# Tricorder-BoosterPack.net
KiCad netlist of a schematic drawn in EAGLE
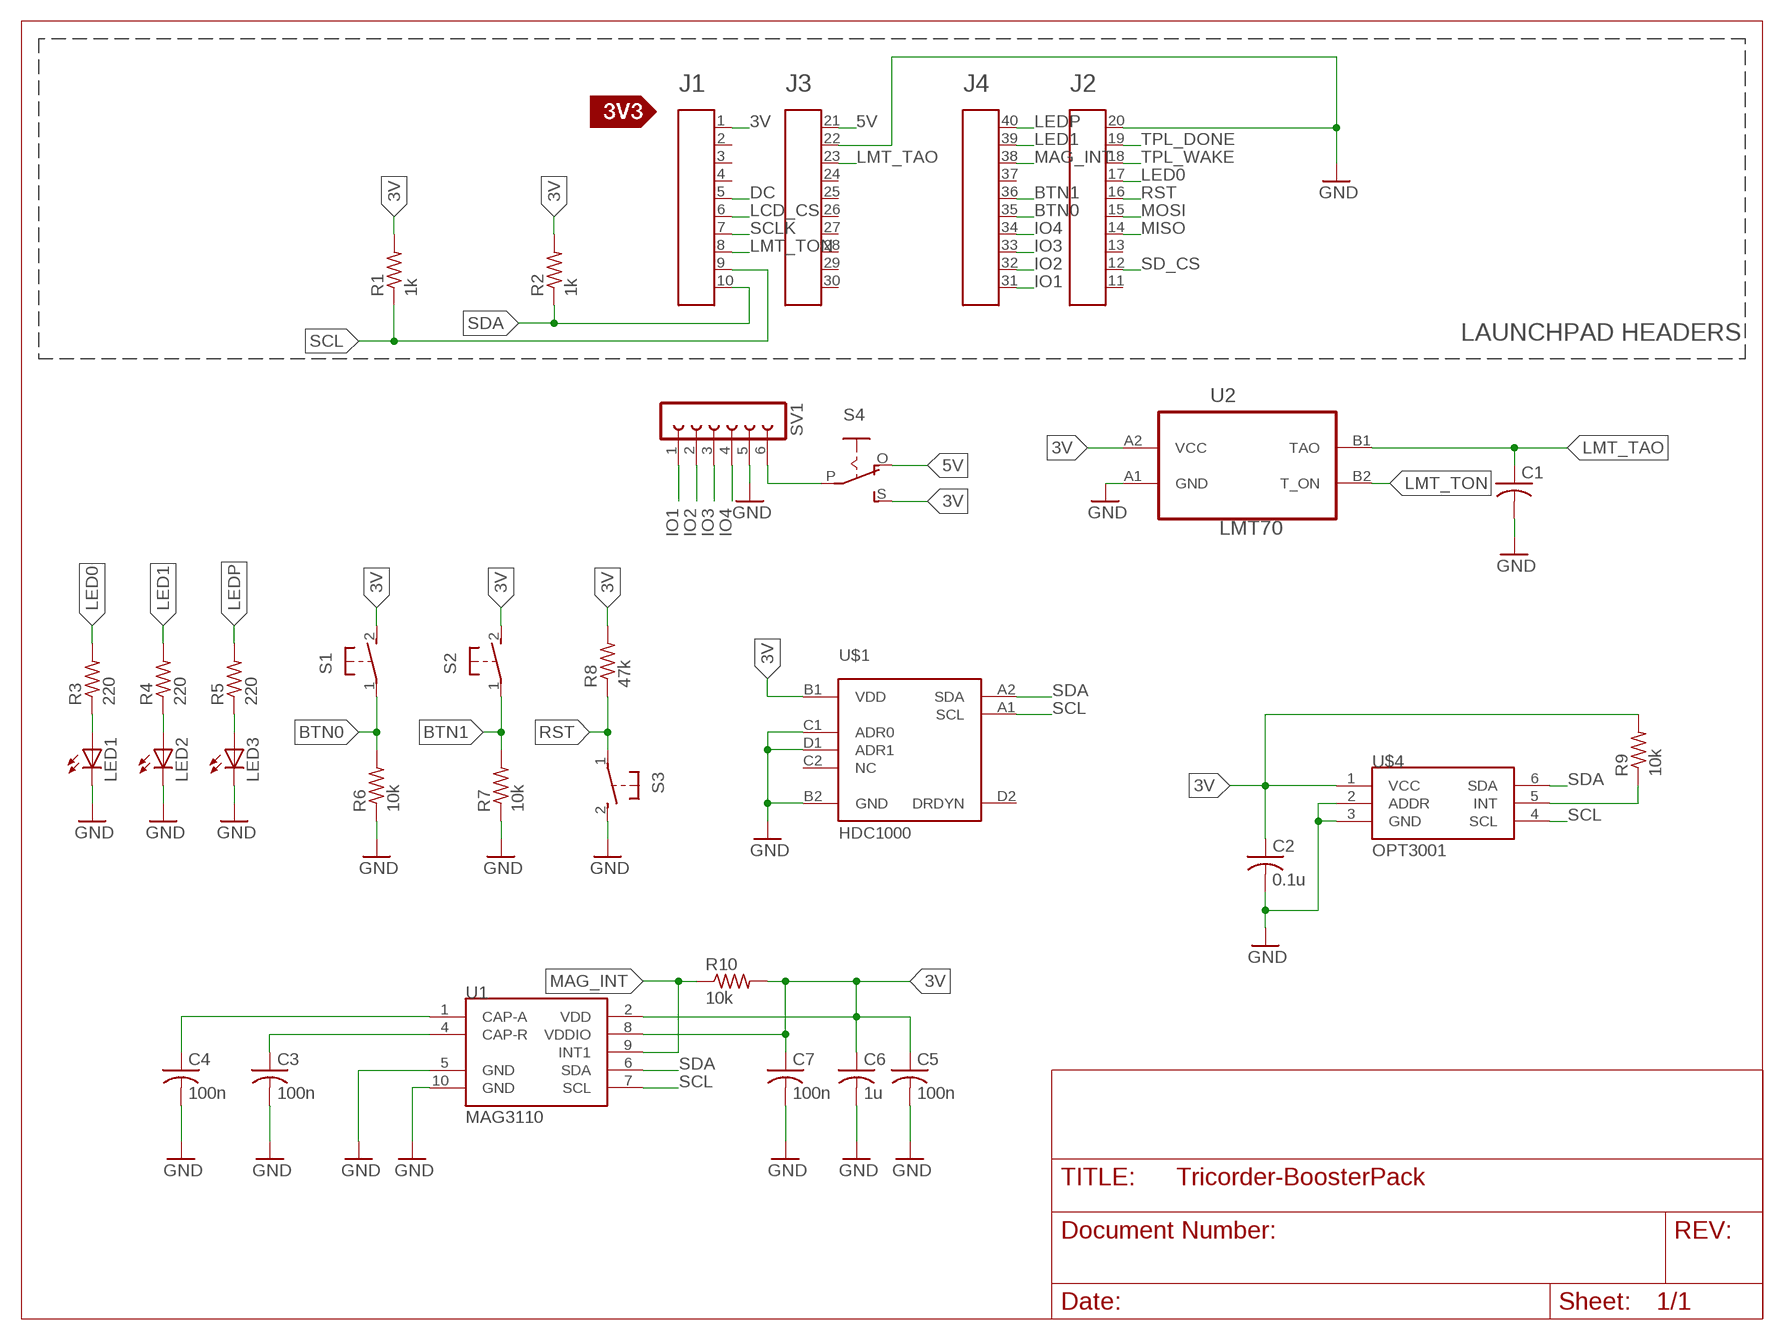
[diagram p0: schematic, sheet 1]

(export (version "E")
  (design (tool "Eeschema 10.0.6"))
  (components
    (comp (ref "A1")
      (value "HEADER4X10-BOOSTERPACK")
      (footprint "eagle-import:4X10-BOOSTERPACK")
      (libsource (lib "eagle-import") (part "HEADER4X10-BOOSTERPACK"))
    )
    (comp (ref "C1")
      (value "C-USC0603")
      (footprint "eagle-import:C0603")
      (libsource (lib "eagle-import") (part "C-USC0603"))
    )
    (comp (ref "C2")
      (value "0.1u")
      (footprint "eagle-import:C0603")
      (libsource (lib "eagle-import") (part "C-USC0603"))
    )
    (comp (ref "C3")
      (value "100n")
      (footprint "eagle-import:C0603")
      (libsource (lib "eagle-import") (part "C-USC0603"))
    )
    (comp (ref "C4")
      (value "100n")
      (footprint "eagle-import:C0603")
      (libsource (lib "eagle-import") (part "C-USC0603"))
    )
    (comp (ref "C5")
      (value "100n")
      (footprint "eagle-import:C0603")
      (libsource (lib "eagle-import") (part "C-USC0603"))
    )
    (comp (ref "C6")
      (value "1u")
      (footprint "eagle-import:C0603")
      (libsource (lib "eagle-import") (part "C-USC0603"))
    )
    (comp (ref "C7")
      (value "100n")
      (footprint "eagle-import:C0603")
      (libsource (lib "eagle-import") (part "C-USC0603"))
    )
    (comp (ref "LED1")
      (value "LEDCHIPLED_0603")
      (footprint "eagle-import:CHIPLED_0603")
      (libsource (lib "eagle-import") (part "LEDCHIPLED_0603"))
    )
    (comp (ref "LED2")
      (value "LEDCHIPLED_0603")
      (footprint "eagle-import:CHIPLED_0603")
      (libsource (lib "eagle-import") (part "LEDCHIPLED_0603"))
    )
    (comp (ref "LED3")
      (value "LEDCHIPLED_0603")
      (footprint "eagle-import:CHIPLED_0603")
      (libsource (lib "eagle-import") (part "LEDCHIPLED_0603"))
    )
    (comp (ref "R1")
      (value "1k")
      (footprint "eagle-import:R0603")
      (libsource (lib "eagle-import") (part "R-US_R0603"))
    )
    (comp (ref "R2")
      (value "1k")
      (footprint "eagle-import:R0603")
      (libsource (lib "eagle-import") (part "R-US_R0603"))
    )
    (comp (ref "R3")
      (value "220")
      (footprint "eagle-import:R0603")
      (libsource (lib "eagle-import") (part "R-US_R0603"))
    )
    (comp (ref "R4")
      (value "220")
      (footprint "eagle-import:R0603")
      (libsource (lib "eagle-import") (part "R-US_R0603"))
    )
    (comp (ref "R5")
      (value "220")
      (footprint "eagle-import:R0603")
      (libsource (lib "eagle-import") (part "R-US_R0603"))
    )
    (comp (ref "R6")
      (value "10k")
      (footprint "eagle-import:R0603")
      (libsource (lib "eagle-import") (part "R-US_R0603"))
    )
    (comp (ref "R7")
      (value "10k")
      (footprint "eagle-import:R0603")
      (libsource (lib "eagle-import") (part "R-US_R0603"))
    )
    (comp (ref "R8")
      (value "47k")
      (footprint "eagle-import:R0603")
      (libsource (lib "eagle-import") (part "R-US_R0603"))
    )
    (comp (ref "R9")
      (value "10k")
      (footprint "eagle-import:R0603")
      (libsource (lib "eagle-import") (part "R-US_R0603"))
    )
    (comp (ref "R10")
      (value "10k")
      (footprint "eagle-import:R0603")
      (libsource (lib "eagle-import") (part "R-US_R0603"))
    )
    (comp (ref "S1")
      (value "31-XX")
      (footprint "eagle-import:B3F-31XX")
      (libsource (lib "eagle-import") (part "31-XX"))
    )
    (comp (ref "S2")
      (value "31-XX")
      (footprint "eagle-import:B3F-31XX")
      (libsource (lib "eagle-import") (part "31-XX"))
    )
    (comp (ref "S3")
      (value "31-XX")
      (footprint "eagle-import:B3F-31XX")
      (libsource (lib "eagle-import") (part "31-XX"))
    )
    (comp (ref "S4")
      (value "EG1218S")
      (footprint "eagle-import:EG1218")
      (libsource (lib "eagle-import") (part "EG1218S"))
    )
    (comp (ref "SV1")
      (value "FE06-1")
      (footprint "eagle-import:FE06")
      (libsource (lib "eagle-import") (part "FE06-1"))
    )
    (comp (ref "U$1")
      (value "HDC1000")
      (footprint "eagle-import:DSBGA_8_YPA")
      (libsource (lib "eagle-import") (part "HDC1000"))
    )
    (comp (ref "U$3")
      (value "SILK_3V3_TAG")
      (footprint "eagle-import:SILK_3V3_TAG")
      (libsource (lib "eagle-import") (part "SILK_3V3_TAG"))
    )
    (comp (ref "U$4")
      (value "OPT3001")
      (footprint "eagle-import:SOT23-6")
      (libsource (lib "eagle-import") (part "OPT3001"))
    )
    (comp (ref "U1")
      (value "MAG3110")
      (footprint "eagle-import:DFN-10")
      (libsource (lib "eagle-import") (part "MAG3110"))
    )
    (comp (ref "U2")
      (value "LMT70LMT70")
      (footprint "eagle-import:BGA4C40P2X2_77X77X50")
      (fields (field (name "MPN") "LMT70"))
      (libsource (lib "eagle-import") (part "LMT70LMT70"))
    )
  )
  (nets
    (net (code "1") (name "/DC") (class "Default")
      (node (ref "A1") (pin "5") (pinfunction "P$5_5") (pintype "bidirectional"))
    )
    (net (code "2") (name "/IO1") (class "Default")
      (node (ref "A1") (pin "31") (pinfunction "P$31_31") (pintype "bidirectional"))
      (node (ref "SV1") (pin "1") (pinfunction "1_1") (pintype "passive"))
    )
    (net (code "3") (name "/IO2") (class "Default")
      (node (ref "A1") (pin "32") (pinfunction "P$32_32") (pintype "bidirectional"))
      (node (ref "SV1") (pin "2") (pinfunction "2_2") (pintype "passive"))
    )
    (net (code "4") (name "/IO3") (class "Default")
      (node (ref "A1") (pin "33") (pinfunction "P$33_33") (pintype "bidirectional"))
      (node (ref "SV1") (pin "3") (pinfunction "3_3") (pintype "passive"))
    )
    (net (code "5") (name "/IO4") (class "Default")
      (node (ref "A1") (pin "34") (pinfunction "P$34_34") (pintype "bidirectional"))
      (node (ref "SV1") (pin "4") (pinfunction "4_4") (pintype "passive"))
    )
    (net (code "6") (name "/LCD_CS") (class "Default")
      (node (ref "A1") (pin "6") (pinfunction "P$6_6") (pintype "bidirectional"))
    )
    (net (code "7") (name "/MISO") (class "Default")
      (node (ref "A1") (pin "14") (pinfunction "P$14_14") (pintype "bidirectional"))
    )
    (net (code "8") (name "/MOSI") (class "Default")
      (node (ref "A1") (pin "15") (pinfunction "P$15_15") (pintype "bidirectional"))
    )
    (net (code "9") (name "/SCLK") (class "Default")
      (node (ref "A1") (pin "7") (pinfunction "P$7_7") (pintype "bidirectional"))
    )
    (net (code "10") (name "/SD_CS") (class "Default")
      (node (ref "A1") (pin "12") (pinfunction "P$12_12") (pintype "bidirectional"))
    )
    (net (code "11") (name "/TPL_DONE") (class "Default")
      (node (ref "A1") (pin "19") (pinfunction "P$19_19") (pintype "bidirectional"))
    )
    (net (code "12") (name "/TPL_WAKE") (class "Default")
      (node (ref "A1") (pin "18") (pinfunction "P$18_18") (pintype "bidirectional"))
    )
    (net (code "13") (name "3V") (class "Default")
      (node (ref "A1") (pin "1") (pinfunction "P$1_1") (pintype "bidirectional"))
      (node (ref "C2") (pin "1") (pinfunction "1_1") (pintype "passive"))
      (node (ref "R1") (pin "2") (pinfunction "2_2") (pintype "passive"))
      (node (ref "R2") (pin "2") (pinfunction "2_2") (pintype "passive"))
      (node (ref "R8") (pin "2") (pinfunction "2_2") (pintype "passive"))
      (node (ref "R9") (pin "2") (pinfunction "2_2") (pintype "passive"))
      (node (ref "S1") (pin "2") (pinfunction "S_2") (pintype "passive"))
      (node (ref "S2") (pin "2") (pinfunction "S_2") (pintype "passive"))
      (node (ref "S4") (pin "S") (pinfunction "S_S") (pintype "passive"))
      (node (ref "U$1") (pin "B1") (pinfunction "VDD_B1") (pintype "power_in"))
      (node (ref "U$4") (pin "1") (pinfunction "VCC_1") (pintype "power_in"))
    )
    (net (code "14") (name "5V") (class "Default")
      (node (ref "A1") (pin "21") (pinfunction "P$21_21") (pintype "bidirectional"))
      (node (ref "S4") (pin "O") (pinfunction "O_O") (pintype "passive"))
    )
    (net (code "15") (name "BTN0") (class "Default")
      (node (ref "A1") (pin "35") (pinfunction "P$35_35") (pintype "bidirectional"))
      (node (ref "R6") (pin "2") (pinfunction "2_2") (pintype "passive"))
      (node (ref "S1") (pin "1") (pinfunction "P_1") (pintype "passive"))
    )
    (net (code "16") (name "BTN1") (class "Default")
      (node (ref "A1") (pin "36") (pinfunction "P$36_36") (pintype "bidirectional"))
      (node (ref "R7") (pin "2") (pinfunction "2_2") (pintype "passive"))
      (node (ref "S2") (pin "1") (pinfunction "P_1") (pintype "passive"))
    )
    (net (code "17") (name "GND") (class "Default")
      (node (ref "A1") (pin "20") (pinfunction "P$20_20") (pintype "bidirectional"))
      (node (ref "A1") (pin "22") (pinfunction "P$22_22") (pintype "bidirectional"))
      (node (ref "C1") (pin "2") (pinfunction "2_2") (pintype "passive"))
      (node (ref "C2") (pin "2") (pinfunction "2_2") (pintype "passive"))
      (node (ref "C3") (pin "2") (pinfunction "2_2") (pintype "passive"))
      (node (ref "C4") (pin "2") (pinfunction "2_2") (pintype "passive"))
      (node (ref "C5") (pin "2") (pinfunction "2_2") (pintype "passive"))
      (node (ref "C6") (pin "2") (pinfunction "2_2") (pintype "passive"))
      (node (ref "C7") (pin "2") (pinfunction "2_2") (pintype "passive"))
      (node (ref "LED1") (pin "C") (pinfunction "C_C") (pintype "passive"))
      (node (ref "LED2") (pin "C") (pinfunction "C_C") (pintype "passive"))
      (node (ref "LED3") (pin "C") (pinfunction "C_C") (pintype "passive"))
      (node (ref "R6") (pin "1") (pinfunction "1_1") (pintype "passive"))
      (node (ref "R7") (pin "1") (pinfunction "1_1") (pintype "passive"))
      (node (ref "S3") (pin "2") (pinfunction "S_2") (pintype "passive"))
      (node (ref "SV1") (pin "5") (pinfunction "5_5") (pintype "passive"))
      (node (ref "U$1") (pin "B2") (pinfunction "GND_B2") (pintype "power_in"))
      (node (ref "U$1") (pin "C1") (pinfunction "ADR0_C1") (pintype "input"))
      (node (ref "U$1") (pin "D1") (pinfunction "ADR1_D1") (pintype "input"))
      (node (ref "U$4") (pin "2") (pinfunction "ADDR_2") (pintype "input"))
      (node (ref "U$4") (pin "3") (pinfunction "GND_3") (pintype "power_in"))
      (node (ref "U1") (pin "10") (pinfunction "GND_10") (pintype "bidirectional"))
      (node (ref "U1") (pin "5") (pinfunction "GND_5") (pintype "bidirectional"))
      (node (ref "U2") (pin "A1") (pinfunction "GND_A1") (pintype "passive"))
    )
    (net (code "18") (name "LED0") (class "Default")
      (node (ref "A1") (pin "17") (pinfunction "P$17_17") (pintype "bidirectional"))
      (node (ref "R3") (pin "2") (pinfunction "2_2") (pintype "passive"))
    )
    (net (code "19") (name "LED1") (class "Default")
      (node (ref "A1") (pin "39") (pinfunction "P$39_39") (pintype "bidirectional"))
      (node (ref "R4") (pin "2") (pinfunction "2_2") (pintype "passive"))
    )
    (net (code "20") (name "LEDP") (class "Default")
      (node (ref "A1") (pin "40") (pinfunction "P$40_40") (pintype "bidirectional"))
      (node (ref "R5") (pin "2") (pinfunction "2_2") (pintype "passive"))
    )
    (net (code "21") (name "LMT_TAO") (class "Default")
      (node (ref "A1") (pin "23") (pinfunction "P$23_23") (pintype "bidirectional"))
      (node (ref "C1") (pin "1") (pinfunction "1_1") (pintype "passive"))
      (node (ref "U2") (pin "B1") (pinfunction "TAO_B1") (pintype "output"))
    )
    (net (code "22") (name "LMT_TON") (class "Default")
      (node (ref "A1") (pin "8") (pinfunction "P$8_8") (pintype "bidirectional"))
      (node (ref "U2") (pin "B2") (pinfunction "T_ON_B2") (pintype "input"))
    )
    (net (code "23") (name "MAG_INT") (class "Default")
      (node (ref "A1") (pin "38") (pinfunction "P$38_38") (pintype "bidirectional"))
      (node (ref "R10") (pin "1") (pinfunction "1_1") (pintype "passive"))
      (node (ref "U1") (pin "9") (pinfunction "INT1_9") (pintype "bidirectional"))
    )
    (net (code "24") (name "Net-(LED1-PadA)") (class "Default")
      (node (ref "LED1") (pin "A") (pinfunction "A_A") (pintype "passive"))
      (node (ref "R3") (pin "1") (pinfunction "1_1") (pintype "passive"))
    )
    (net (code "25") (name "Net-(LED2-PadA)") (class "Default")
      (node (ref "LED2") (pin "A") (pinfunction "A_A") (pintype "passive"))
      (node (ref "R4") (pin "1") (pinfunction "1_1") (pintype "passive"))
    )
    (net (code "26") (name "Net-(LED3-PadA)") (class "Default")
      (node (ref "LED3") (pin "A") (pinfunction "A_A") (pintype "passive"))
      (node (ref "R5") (pin "1") (pinfunction "1_1") (pintype "passive"))
    )
    (net (code "27") (name "Net-(S4-PadP)") (class "Default")
      (node (ref "S4") (pin "P") (pinfunction "P_P") (pintype "passive"))
      (node (ref "SV1") (pin "6") (pinfunction "6_6") (pintype "passive"))
    )
    (net (code "28") (name "Net-(U$4-INT)") (class "Default")
      (node (ref "R9") (pin "1") (pinfunction "1_1") (pintype "passive"))
      (node (ref "U$4") (pin "5") (pinfunction "INT_5") (pintype "output"))
    )
    (net (code "29") (name "Net-(U1-CAP-A)") (class "Default")
      (node (ref "C4") (pin "1") (pinfunction "1_1") (pintype "passive"))
      (node (ref "U1") (pin "1") (pinfunction "CAP-A_1") (pintype "bidirectional"))
    )
    (net (code "30") (name "Net-(U1-CAP-R)") (class "Default")
      (node (ref "C3") (pin "1") (pinfunction "1_1") (pintype "passive"))
      (node (ref "U1") (pin "4") (pinfunction "CAP-R_4") (pintype "bidirectional"))
    )
    (net (code "31") (name "Net-(U1-VDD)") (class "Default")
      (node (ref "C5") (pin "1") (pinfunction "1_1") (pintype "passive"))
      (node (ref "C6") (pin "1") (pinfunction "1_1") (pintype "passive"))
      (node (ref "C7") (pin "1") (pinfunction "1_1") (pintype "passive"))
      (node (ref "R10") (pin "2") (pinfunction "2_2") (pintype "passive"))
      (node (ref "U1") (pin "2") (pinfunction "VDD_2") (pintype "bidirectional"))
      (node (ref "U1") (pin "8") (pinfunction "VDDIO_8") (pintype "bidirectional"))
    )
    (net (code "32") (name "RST") (class "Default")
      (node (ref "A1") (pin "16") (pinfunction "P$16_16") (pintype "bidirectional"))
      (node (ref "R8") (pin "1") (pinfunction "1_1") (pintype "passive"))
      (node (ref "S3") (pin "1") (pinfunction "P_1") (pintype "passive"))
    )
    (net (code "33") (name "SCL") (class "Default")
      (node (ref "A1") (pin "9") (pinfunction "P$9_9") (pintype "bidirectional"))
      (node (ref "R1") (pin "1") (pinfunction "1_1") (pintype "passive"))
      (node (ref "U$1") (pin "A1") (pinfunction "SCL_A1") (pintype "input"))
      (node (ref "U$4") (pin "4") (pinfunction "SCL_4") (pintype "input"))
      (node (ref "U1") (pin "7") (pinfunction "SCL_7") (pintype "bidirectional"))
    )
    (net (code "34") (name "SDA") (class "Default")
      (node (ref "A1") (pin "10") (pinfunction "P$10_10") (pintype "bidirectional"))
      (node (ref "R2") (pin "1") (pinfunction "1_1") (pintype "passive"))
      (node (ref "U$1") (pin "A2") (pinfunction "SDA_A2") (pintype "bidirectional"))
      (node (ref "U$4") (pin "6") (pinfunction "SDA_6") (pintype "input"))
      (node (ref "U1") (pin "6") (pinfunction "SDA_6") (pintype "bidirectional"))
    )
    (net (code "35") (name "unconnected-(A1-P$2-Pad2)") (class "Default")
      (node (ref "A1") (pin "2") (pinfunction "P$2_2") (pintype "bidirectional"))
    )
    (net (code "36") (name "unconnected-(A1-P$3-Pad3)") (class "Default")
      (node (ref "A1") (pin "3") (pinfunction "P$3_3") (pintype "bidirectional"))
    )
    (net (code "37") (name "unconnected-(A1-P$4-Pad4)") (class "Default")
      (node (ref "A1") (pin "4") (pinfunction "P$4_4") (pintype "bidirectional"))
    )
    (net (code "38") (name "unconnected-(A1-P$11-Pad11)") (class "Default")
      (node (ref "A1") (pin "11") (pinfunction "P$11_11") (pintype "bidirectional"))
    )
    (net (code "39") (name "unconnected-(A1-P$13-Pad13)") (class "Default")
      (node (ref "A1") (pin "13") (pinfunction "P$13_13") (pintype "bidirectional"))
    )
    (net (code "40") (name "unconnected-(A1-P$24-Pad24)") (class "Default")
      (node (ref "A1") (pin "24") (pinfunction "P$24_24") (pintype "bidirectional"))
    )
    (net (code "41") (name "unconnected-(A1-P$25-Pad25)") (class "Default")
      (node (ref "A1") (pin "25") (pinfunction "P$25_25") (pintype "bidirectional"))
    )
    (net (code "42") (name "unconnected-(A1-P$26-Pad26)") (class "Default")
      (node (ref "A1") (pin "26") (pinfunction "P$26_26") (pintype "bidirectional"))
    )
    (net (code "43") (name "unconnected-(A1-P$27-Pad27)") (class "Default")
      (node (ref "A1") (pin "27") (pinfunction "P$27_27") (pintype "bidirectional"))
    )
    (net (code "44") (name "unconnected-(A1-P$28-Pad28)") (class "Default")
      (node (ref "A1") (pin "28") (pinfunction "P$28_28") (pintype "bidirectional"))
    )
    (net (code "45") (name "unconnected-(A1-P$29-Pad29)") (class "Default")
      (node (ref "A1") (pin "29") (pinfunction "P$29_29") (pintype "bidirectional"))
    )
    (net (code "46") (name "unconnected-(A1-P$30-Pad30)") (class "Default")
      (node (ref "A1") (pin "30") (pinfunction "P$30_30") (pintype "bidirectional"))
    )
    (net (code "47") (name "unconnected-(A1-P$37-Pad37)") (class "Default")
      (node (ref "A1") (pin "37") (pinfunction "P$37_37") (pintype "bidirectional"))
    )
    (net (code "48") (name "unconnected-(U$1-DRDYN-PadD2)") (class "Default")
      (node (ref "U$1") (pin "D2") (pinfunction "DRDYN_D2") (pintype "output"))
    )
    (net (code "49") (name "unconnected-(U$1-NC-PadC2)") (class "Default")
      (node (ref "U$1") (pin "C2") (pinfunction "NC_C2") (pintype "no_connect"))
    )
    (net (code "50") (name "unconnected-(U2-VCC-PadA2)") (class "Default")
      (node (ref "U2") (pin "A2") (pinfunction "VCC_A2") (pintype "power_in"))
    )
  )
)
